# lcd_16_2.net
KiCad netlist of a schematic drawn in Altium Designer
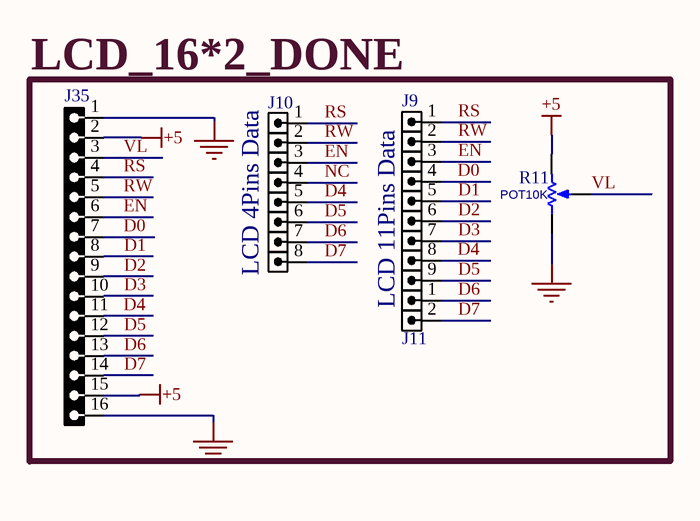
[diagram p0: lcd_16_2.SchDoc]

(export (version "E")
  (design (tool "Eeschema 10.0.6"))
  (components
    (comp (ref "J9")
      (value "HDR1X9")
      (footprint "HDR_M_1X9")
      (description "CONN, HEADER, Male, pitch: 2.54mm, 9POS")
      (libsource (lib "conn_header_2.54mm_st") (part "HDR_M_1X9"))
    )
    (comp (ref "J10")
      (value "HDR1X8")
      (footprint "HDR_M_1X8")
      (description "CONN, HEADER, Male, pitch: 2.54mm, 8POS")
      (libsource (lib "conn_header_2.54mm_st") (part "HDR_M_1X8"))
    )
    (comp (ref "J11")
      (value "HDRM2")
      (footprint "HDR_M_1X2")
      (description "CONN, HEADER, Male, pitch: 2.54mm, 2POS")
      (libsource (lib "conn_header_2.54mm_st") (part "HDR_M_1X2"))
    )
    (comp (ref "J35")
      (value "HDRF16")
      (footprint "HDR_F_1X16")
      (description "CONN, HEADER, Female, pitch: 2.54mm, 16POS")
      (libsource (lib "conn_header_2.54mm_st") (part "HDR_F_1X16"))
    )
    (comp (ref "R11")
      (value "POT10K")
      (footprint "POT_7X5")
      (description "RESISTOR, THD, Potentiometer")
      (libsource (lib "resistor_pot_trimmer") (part "RES_THD_POT_7X5"))
    )
  )
  (nets
    (net (code "1") (name "+5") (class "Default")
      (node (ref "J35") (pin "15") (pinfunction "15_15") (pintype "passive"))
      (node (ref "J35") (pin "2") (pinfunction "2_2") (pintype "passive"))
      (node (ref "R11") (pin "3") (pinfunction "BOT_3") (pintype "passive"))
    )
    (net (code "2") (name "/D0") (class "Default")
      (node (ref "J35") (pin "7") (pinfunction "7_7") (pintype "passive"))
      (node (ref "J9") (pin "4") (pinfunction "4_4") (pintype "passive"))
    )
    (net (code "3") (name "/D1") (class "Default")
      (node (ref "J35") (pin "8") (pinfunction "8_8") (pintype "passive"))
      (node (ref "J9") (pin "5") (pinfunction "5_5") (pintype "passive"))
    )
    (net (code "4") (name "/D2") (class "Default")
      (node (ref "J35") (pin "9") (pinfunction "9_9") (pintype "passive"))
      (node (ref "J9") (pin "6") (pinfunction "6_6") (pintype "passive"))
    )
    (net (code "5") (name "/D3") (class "Default")
      (node (ref "J35") (pin "10") (pinfunction "10_10") (pintype "passive"))
      (node (ref "J9") (pin "7") (pinfunction "7_7") (pintype "passive"))
    )
    (net (code "6") (name "/D4") (class "Default")
      (node (ref "J10") (pin "5") (pinfunction "5_5") (pintype "passive"))
      (node (ref "J35") (pin "11") (pinfunction "11_11") (pintype "passive"))
      (node (ref "J9") (pin "8") (pinfunction "8_8") (pintype "passive"))
    )
    (net (code "7") (name "/D5") (class "Default")
      (node (ref "J10") (pin "6") (pinfunction "6_6") (pintype "passive"))
      (node (ref "J35") (pin "12") (pinfunction "12_12") (pintype "passive"))
      (node (ref "J9") (pin "9") (pinfunction "9_9") (pintype "passive"))
    )
    (net (code "8") (name "/D6") (class "Default")
      (node (ref "J10") (pin "7") (pinfunction "7_7") (pintype "passive"))
      (node (ref "J11") (pin "1") (pinfunction "1_1") (pintype "passive"))
      (node (ref "J35") (pin "13") (pinfunction "13_13") (pintype "passive"))
    )
    (net (code "9") (name "/D7") (class "Default")
      (node (ref "J10") (pin "8") (pinfunction "8_8") (pintype "passive"))
      (node (ref "J11") (pin "2") (pinfunction "2_2") (pintype "passive"))
      (node (ref "J35") (pin "14") (pinfunction "14_14") (pintype "passive"))
    )
    (net (code "10") (name "/EN") (class "Default")
      (node (ref "J10") (pin "3") (pinfunction "3_3") (pintype "passive"))
      (node (ref "J35") (pin "6") (pinfunction "6_6") (pintype "passive"))
      (node (ref "J9") (pin "3") (pinfunction "3_3") (pintype "passive"))
    )
    (net (code "11") (name "/NC") (class "Default")
      (node (ref "J10") (pin "4") (pinfunction "4_4") (pintype "passive"))
    )
    (net (code "12") (name "/RS") (class "Default")
      (node (ref "J10") (pin "1") (pinfunction "1_1") (pintype "passive"))
      (node (ref "J35") (pin "4") (pinfunction "4_4") (pintype "passive"))
      (node (ref "J9") (pin "1") (pinfunction "1_1") (pintype "passive"))
    )
    (net (code "13") (name "/RW") (class "Default")
      (node (ref "J10") (pin "2") (pinfunction "2_2") (pintype "passive"))
      (node (ref "J35") (pin "5") (pinfunction "5_5") (pintype "passive"))
      (node (ref "J9") (pin "2") (pinfunction "2_2") (pintype "passive"))
    )
    (net (code "14") (name "/VL") (class "Default")
      (node (ref "J35") (pin "3") (pinfunction "3_3") (pintype "passive"))
      (node (ref "R11") (pin "2") (pinfunction "TAP_2") (pintype "passive"))
    )
    (net (code "15") (name "GND") (class "Default")
      (node (ref "J35") (pin "1") (pinfunction "1_1") (pintype "passive"))
      (node (ref "J35") (pin "16") (pinfunction "16_16") (pintype "passive"))
      (node (ref "R11") (pin "1") (pinfunction "TOP_1") (pintype "passive"))
    )
  )
)
